# ESC.net
KiCad netlist of a schematic drawn in EAGLE
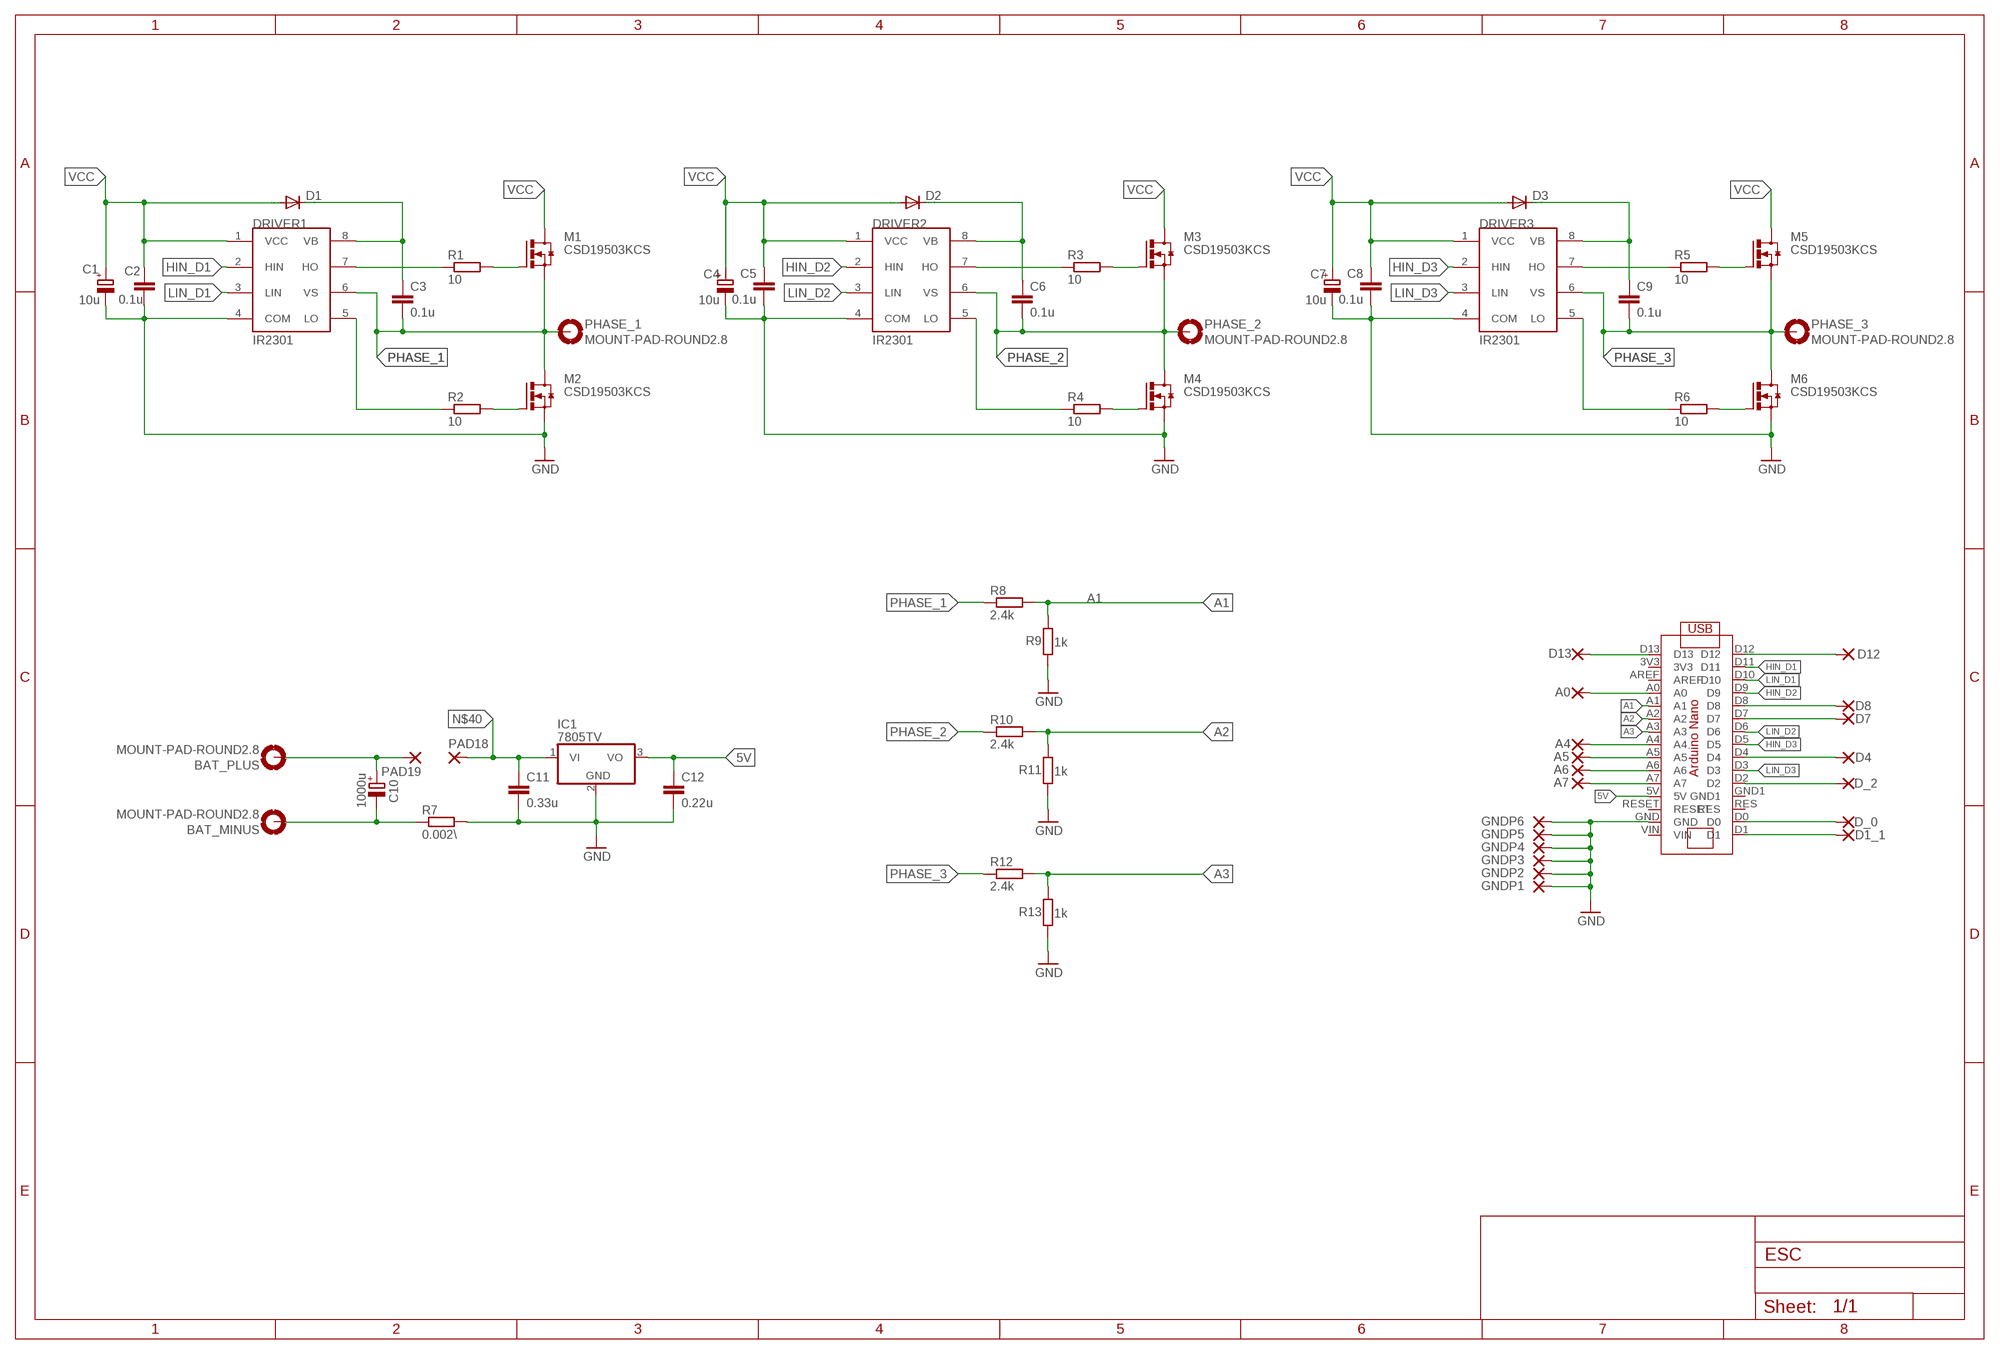
[diagram p0: schematic, sheet 1]

(export (version "E")
  (design (tool "Eeschema 10.0.6"))
  (components
    (comp (ref "A0")
      (value "3,81/1,4")
      (footprint "eagle-import:3,81_1,4")
      (libsource (lib "eagle-import") (part "3,81/1,4"))
    )
    (comp (ref "A4")
      (value "3,81/1,4")
      (footprint "eagle-import:3,81_1,4")
      (libsource (lib "eagle-import") (part "3,81/1,4"))
    )
    (comp (ref "A5")
      (value "3,81/1,4")
      (footprint "eagle-import:3,81_1,4")
      (libsource (lib "eagle-import") (part "3,81/1,4"))
    )
    (comp (ref "A6")
      (value "3,81/1,4")
      (footprint "eagle-import:3,81_1,4")
      (libsource (lib "eagle-import") (part "3,81/1,4"))
    )
    (comp (ref "A7")
      (value "3,81/1,4")
      (footprint "eagle-import:3,81_1,4")
      (libsource (lib "eagle-import") (part "3,81/1,4"))
    )
    (comp (ref "BAT_MINUS")
      (value "MOUNT-PAD-ROUND2.8")
      (footprint "eagle-import:2,8-PAD")
      (libsource (lib "eagle-import") (part "MOUNT-PAD-ROUND2.8"))
    )
    (comp (ref "BAT_PLUS")
      (value "MOUNT-PAD-ROUND2.8")
      (footprint "eagle-import:2,8-PAD")
      (libsource (lib "eagle-import") (part "MOUNT-PAD-ROUND2.8"))
    )
    (comp (ref "C1")
      (value "10u")
      (footprint "eagle-import:PANASONIC_C")
      (libsource (lib "eagle-import") (part "CPOL-EUC"))
    )
    (comp (ref "C2")
      (value "0.1u")
      (footprint "eagle-import:C1206")
      (libsource (lib "eagle-import") (part "CC1206"))
    )
    (comp (ref "C3")
      (value "0.1u")
      (footprint "eagle-import:C1206")
      (libsource (lib "eagle-import") (part "CC1206"))
    )
    (comp (ref "C4")
      (value "10u")
      (footprint "eagle-import:PANASONIC_C")
      (libsource (lib "eagle-import") (part "CPOL-EUC"))
    )
    (comp (ref "C5")
      (value "0.1u")
      (footprint "eagle-import:C1206")
      (libsource (lib "eagle-import") (part "CC1206"))
    )
    (comp (ref "C6")
      (value "0.1u")
      (footprint "eagle-import:C1206")
      (libsource (lib "eagle-import") (part "CC1206"))
    )
    (comp (ref "C7")
      (value "10u")
      (footprint "eagle-import:PANASONIC_C")
      (libsource (lib "eagle-import") (part "CPOL-EUC"))
    )
    (comp (ref "C8")
      (value "0.1u")
      (footprint "eagle-import:C1206")
      (libsource (lib "eagle-import") (part "CC1206"))
    )
    (comp (ref "C9")
      (value "0.1u")
      (footprint "eagle-import:C1206")
      (libsource (lib "eagle-import") (part "CC1206"))
    )
    (comp (ref "C10")
      (value "1000u")
      (footprint "eagle-import:E7,5-16")
      (libsource (lib "eagle-import") (part "CPOL-EUE7.5-16"))
    )
    (comp (ref "C11")
      (value "0.33u")
      (footprint "eagle-import:C1206")
      (libsource (lib "eagle-import") (part "CC1206"))
    )
    (comp (ref "C12")
      (value "0.22u")
      (footprint "eagle-import:C1206")
      (libsource (lib "eagle-import") (part "CC1206"))
    )
    (comp (ref "D1")
      (value "DIODE-DO41-10")
      (footprint "eagle-import:DO41-10")
      (libsource (lib "eagle-import") (part "DIODE-DO41-10"))
    )
    (comp (ref "D1_1")
      (value "3,81/1,4")
      (footprint "eagle-import:3,81_1,4")
      (libsource (lib "eagle-import") (part "3,81/1,4"))
    )
    (comp (ref "D2")
      (value "DIODE-DO41-10")
      (footprint "eagle-import:DO41-10")
      (libsource (lib "eagle-import") (part "DIODE-DO41-10"))
    )
    (comp (ref "D3")
      (value "DIODE-DO41-10")
      (footprint "eagle-import:DO41-10")
      (libsource (lib "eagle-import") (part "DIODE-DO41-10"))
    )
    (comp (ref "D4")
      (value "3,81/1,4")
      (footprint "eagle-import:3,81_1,4")
      (libsource (lib "eagle-import") (part "3,81/1,4"))
    )
    (comp (ref "D7")
      (value "3,81/1,4")
      (footprint "eagle-import:3,81_1,4")
      (libsource (lib "eagle-import") (part "3,81/1,4"))
    )
    (comp (ref "D8")
      (value "3,81/1,4")
      (footprint "eagle-import:3,81_1,4")
      (libsource (lib "eagle-import") (part "3,81/1,4"))
    )
    (comp (ref "D12")
      (value "3,81/1,4")
      (footprint "eagle-import:3,81_1,4")
      (libsource (lib "eagle-import") (part "3,81/1,4"))
    )
    (comp (ref "D13")
      (value "3,81/1,4")
      (footprint "eagle-import:3,81_1,4")
      (libsource (lib "eagle-import") (part "3,81/1,4"))
    )
    (comp (ref "DRIVER1")
      (value "IR2301")
      (footprint "eagle-import:DIL08")
      (fields (field (name "MF") "Infineon"))
      (libsource (lib "eagle-import") (part "IR2301"))
    )
    (comp (ref "DRIVER2")
      (value "IR2301")
      (footprint "eagle-import:DIL08")
      (fields (field (name "MF") "Infineon"))
      (libsource (lib "eagle-import") (part "IR2301"))
    )
    (comp (ref "DRIVER3")
      (value "IR2301")
      (footprint "eagle-import:DIL08")
      (fields (field (name "MF") "Infineon"))
      (libsource (lib "eagle-import") (part "IR2301"))
    )
    (comp (ref "D_0")
      (value "3,81/1,4")
      (footprint "eagle-import:3,81_1,4")
      (libsource (lib "eagle-import") (part "3,81/1,4"))
    )
    (comp (ref "D_2")
      (value "3,81/1,4")
      (footprint "eagle-import:3,81_1,4")
      (libsource (lib "eagle-import") (part "3,81/1,4"))
    )
    (comp (ref "GNDP1")
      (value "3,81/1,4")
      (footprint "eagle-import:3,81_1,4")
      (libsource (lib "eagle-import") (part "3,81/1,4"))
    )
    (comp (ref "GNDP2")
      (value "3,81/1,4")
      (footprint "eagle-import:3,81_1,4")
      (libsource (lib "eagle-import") (part "3,81/1,4"))
    )
    (comp (ref "GNDP3")
      (value "3,81/1,4")
      (footprint "eagle-import:3,81_1,4")
      (libsource (lib "eagle-import") (part "3,81/1,4"))
    )
    (comp (ref "GNDP4")
      (value "3,81/1,4")
      (footprint "eagle-import:3,81_1,4")
      (libsource (lib "eagle-import") (part "3,81/1,4"))
    )
    (comp (ref "GNDP5")
      (value "3,81/1,4")
      (footprint "eagle-import:3,81_1,4")
      (libsource (lib "eagle-import") (part "3,81/1,4"))
    )
    (comp (ref "GNDP6")
      (value "3,81/1,4")
      (footprint "eagle-import:3,81_1,4")
      (libsource (lib "eagle-import") (part "3,81/1,4"))
    )
    (comp (ref "IC1")
      (value "7805TV")
      (footprint "eagle-import:TO220V")
      (libsource (lib "eagle-import") (part "78TV05"))
    )
    (comp (ref "M1")
      (value "CSD19503KCS")
      (footprint "eagle-import:TO220BV")
      (fields (field (name "SPICEPREFIX") "M"))
      (libsource (lib "eagle-import") (part "CSD19503KCS"))
    )
    (comp (ref "M2")
      (value "CSD19503KCS")
      (footprint "eagle-import:TO220BV")
      (libsource (lib "eagle-import") (part "CSD19503KCS"))
    )
    (comp (ref "M3")
      (value "CSD19503KCS")
      (footprint "eagle-import:TO220BV")
      (libsource (lib "eagle-import") (part "CSD19503KCS"))
    )
    (comp (ref "M4")
      (value "CSD19503KCS")
      (footprint "eagle-import:TO220BV")
      (libsource (lib "eagle-import") (part "CSD19503KCS"))
    )
    (comp (ref "M5")
      (value "CSD19503KCS")
      (footprint "eagle-import:TO220BV")
      (libsource (lib "eagle-import") (part "CSD19503KCS"))
    )
    (comp (ref "M6")
      (value "CSD19503KCS")
      (footprint "eagle-import:TO220BV")
      (libsource (lib "eagle-import") (part "CSD19503KCS"))
    )
    (comp (ref "PAD18")
      (value "3,81/1,4")
      (footprint "eagle-import:3,81_1,4")
      (libsource (lib "eagle-import") (part "3,81/1,4"))
    )
    (comp (ref "PAD19")
      (value "3,81/1,4")
      (footprint "eagle-import:3,81_1,4")
      (libsource (lib "eagle-import") (part "3,81/1,4"))
    )
    (comp (ref "PHASE_1")
      (value "MOUNT-PAD-ROUND2.8")
      (footprint "eagle-import:2,8-PAD")
      (libsource (lib "eagle-import") (part "MOUNT-PAD-ROUND2.8"))
    )
    (comp (ref "PHASE_2")
      (value "MOUNT-PAD-ROUND2.8")
      (footprint "eagle-import:2,8-PAD")
      (libsource (lib "eagle-import") (part "MOUNT-PAD-ROUND2.8"))
    )
    (comp (ref "PHASE_3")
      (value "MOUNT-PAD-ROUND2.8")
      (footprint "eagle-import:2,8-PAD")
      (libsource (lib "eagle-import") (part "MOUNT-PAD-ROUND2.8"))
    )
    (comp (ref "R1")
      (value "10")
      (footprint "eagle-import:R1206")
      (libsource (lib "eagle-import") (part "R-EU_R1206"))
    )
    (comp (ref "R2")
      (value "10")
      (footprint "eagle-import:R1206")
      (libsource (lib "eagle-import") (part "R-EU_R1206"))
    )
    (comp (ref "R3")
      (value "10")
      (footprint "eagle-import:R1206")
      (libsource (lib "eagle-import") (part "R-EU_R1206"))
    )
    (comp (ref "R4")
      (value "10")
      (footprint "eagle-import:R1206")
      (libsource (lib "eagle-import") (part "R-EU_R1206"))
    )
    (comp (ref "R5")
      (value "10")
      (footprint "eagle-import:R1206")
      (libsource (lib "eagle-import") (part "R-EU_R1206"))
    )
    (comp (ref "R6")
      (value "10")
      (footprint "eagle-import:R1206")
      (libsource (lib "eagle-import") (part "R-EU_R1206"))
    )
    (comp (ref "R7")
      (value "0.002\\")
      (footprint "eagle-import:R2512")
      (libsource (lib "eagle-import") (part "R-EU_R2512"))
    )
    (comp (ref "R8")
      (value "2.4k")
      (footprint "eagle-import:R1206")
      (libsource (lib "eagle-import") (part "R-EU_R1206"))
    )
    (comp (ref "R9")
      (value "1k")
      (footprint "eagle-import:R1206")
      (libsource (lib "eagle-import") (part "R-EU_R1206"))
    )
    (comp (ref "R10")
      (value "2.4k")
      (footprint "eagle-import:R1206")
      (libsource (lib "eagle-import") (part "R-EU_R1206"))
    )
    (comp (ref "R11")
      (value "1k")
      (footprint "eagle-import:R1206")
      (libsource (lib "eagle-import") (part "R-EU_R1206"))
    )
    (comp (ref "R12")
      (value "2.4k")
      (footprint "eagle-import:R1206")
      (libsource (lib "eagle-import") (part "R-EU_R1206"))
    )
    (comp (ref "R13")
      (value "1k")
      (footprint "eagle-import:R1206")
      (libsource (lib "eagle-import") (part "R-EU_R1206"))
    )
    (comp (ref "U$7")
      (value "ARDUINO-NANO")
      (footprint "eagle-import:ARDUINO-NANO")
      (libsource (lib "eagle-import") (part "ARDUINO-NANO"))
    )
  )
  (nets
    (net (code "1") (name "5V") (class "Default")
      (node (ref "C12") (pin "1") (pinfunction "1_1") (pintype "passive"))
      (node (ref "IC1") (pin "3") (pinfunction "VO_3") (pintype "passive"))
      (node (ref "U$7") (pin "5V") (pinfunction "5V_5V") (pintype "bidirectional"))
    )
    (net (code "2") (name "A1") (class "Default")
      (node (ref "R8") (pin "2") (pinfunction "2_2") (pintype "bidirectional"))
      (node (ref "R9") (pin "2") (pinfunction "2_2") (pintype "bidirectional"))
      (node (ref "U$7") (pin "A1") (pinfunction "A1_A1") (pintype "bidirectional"))
    )
    (net (code "3") (name "A2") (class "Default")
      (node (ref "R10") (pin "2") (pinfunction "2_2") (pintype "bidirectional"))
      (node (ref "R11") (pin "2") (pinfunction "2_2") (pintype "bidirectional"))
      (node (ref "U$7") (pin "A2") (pinfunction "A2_A2") (pintype "bidirectional"))
    )
    (net (code "4") (name "A3") (class "Default")
      (node (ref "R12") (pin "2") (pinfunction "2_2") (pintype "bidirectional"))
      (node (ref "R13") (pin "2") (pinfunction "2_2") (pintype "bidirectional"))
      (node (ref "U$7") (pin "A3") (pinfunction "A3_A3") (pintype "bidirectional"))
    )
    (net (code "5") (name "GND") (class "Default")
      (node (ref "C1") (pin "-") (pinfunction "-_-") (pintype "passive"))
      (node (ref "C11") (pin "2") (pinfunction "2_2") (pintype "passive"))
      (node (ref "C12") (pin "2") (pinfunction "2_2") (pintype "passive"))
      (node (ref "C2") (pin "2") (pinfunction "2_2") (pintype "passive"))
      (node (ref "C4") (pin "-") (pinfunction "-_-") (pintype "passive"))
      (node (ref "C5") (pin "2") (pinfunction "2_2") (pintype "passive"))
      (node (ref "C7") (pin "-") (pinfunction "-_-") (pintype "passive"))
      (node (ref "C8") (pin "2") (pinfunction "2_2") (pintype "passive"))
      (node (ref "DRIVER1") (pin "4") (pinfunction "COM_4") (pintype "power_in"))
      (node (ref "DRIVER2") (pin "4") (pinfunction "COM_4") (pintype "power_in"))
      (node (ref "DRIVER3") (pin "4") (pinfunction "COM_4") (pintype "power_in"))
      (node (ref "GNDP1") (pin "1") (pinfunction "P_1") (pintype "passive"))
      (node (ref "GNDP2") (pin "1") (pinfunction "P_1") (pintype "passive"))
      (node (ref "GNDP3") (pin "1") (pinfunction "P_1") (pintype "passive"))
      (node (ref "GNDP4") (pin "1") (pinfunction "P_1") (pintype "passive"))
      (node (ref "GNDP5") (pin "1") (pinfunction "P_1") (pintype "passive"))
      (node (ref "GNDP6") (pin "1") (pinfunction "P_1") (pintype "passive"))
      (node (ref "IC1") (pin "2") (pinfunction "GND_2") (pintype "passive"))
      (node (ref "M2") (pin "S") (pinfunction "S_S") (pintype "passive"))
      (node (ref "M4") (pin "S") (pinfunction "S_S") (pintype "passive"))
      (node (ref "M6") (pin "S") (pinfunction "S_S") (pintype "passive"))
      (node (ref "R11") (pin "1") (pinfunction "1_1") (pintype "bidirectional"))
      (node (ref "R13") (pin "1") (pinfunction "1_1") (pintype "bidirectional"))
      (node (ref "R7") (pin "2") (pinfunction "2_2") (pintype "passive"))
      (node (ref "R9") (pin "1") (pinfunction "1_1") (pintype "bidirectional"))
      (node (ref "U$7") (pin "GND") (pinfunction "GND_GND") (pintype "bidirectional"))
    )
    (net (code "6") (name "HIN_D1") (class "Default")
      (node (ref "DRIVER1") (pin "2") (pinfunction "HIN_2") (pintype "input"))
      (node (ref "U$7") (pin "D11") (pinfunction "D11_D11") (pintype "bidirectional"))
    )
    (net (code "7") (name "HIN_D2") (class "Default")
      (node (ref "DRIVER2") (pin "2") (pinfunction "HIN_2") (pintype "input"))
      (node (ref "U$7") (pin "D9") (pinfunction "D9_D9") (pintype "bidirectional"))
    )
    (net (code "8") (name "HIN_D3") (class "Default")
      (node (ref "DRIVER3") (pin "2") (pinfunction "HIN_2") (pintype "input"))
      (node (ref "U$7") (pin "D5") (pinfunction "D5_D5") (pintype "bidirectional"))
    )
    (net (code "9") (name "LIN_D1") (class "Default")
      (node (ref "DRIVER1") (pin "3") (pinfunction "LIN_3") (pintype "input"))
      (node (ref "U$7") (pin "D10") (pinfunction "D10_D10") (pintype "bidirectional"))
    )
    (net (code "10") (name "LIN_D2") (class "Default")
      (node (ref "DRIVER2") (pin "3") (pinfunction "LIN_3") (pintype "input"))
      (node (ref "U$7") (pin "D6") (pinfunction "D6_D6") (pintype "bidirectional"))
    )
    (net (code "11") (name "LIN_D3") (class "Default")
      (node (ref "DRIVER3") (pin "3") (pinfunction "LIN_3") (pintype "input"))
      (node (ref "U$7") (pin "D3") (pinfunction "D3_D3") (pintype "bidirectional"))
    )
    (net (code "12") (name "N$40") (class "Default")
      (node (ref "C11") (pin "1") (pinfunction "1_1") (pintype "passive"))
      (node (ref "IC1") (pin "1") (pinfunction "VI_1") (pintype "input"))
      (node (ref "PAD18") (pin "1") (pinfunction "P_1") (pintype "passive"))
    )
    (net (code "13") (name "Net-(A0-P)") (class "Default")
      (node (ref "A0") (pin "1") (pinfunction "P_1") (pintype "passive"))
      (node (ref "U$7") (pin "A0") (pinfunction "A0_A0") (pintype "bidirectional"))
    )
    (net (code "14") (name "Net-(A4-P)") (class "Default")
      (node (ref "A4") (pin "1") (pinfunction "P_1") (pintype "passive"))
      (node (ref "U$7") (pin "A4") (pinfunction "A4_A4") (pintype "bidirectional"))
    )
    (net (code "15") (name "Net-(A5-P)") (class "Default")
      (node (ref "A5") (pin "1") (pinfunction "P_1") (pintype "passive"))
      (node (ref "U$7") (pin "A5") (pinfunction "A5_A5") (pintype "bidirectional"))
    )
    (net (code "16") (name "Net-(A6-P)") (class "Default")
      (node (ref "A6") (pin "1") (pinfunction "P_1") (pintype "passive"))
      (node (ref "U$7") (pin "A6") (pinfunction "A6_A6") (pintype "bidirectional"))
    )
    (net (code "17") (name "Net-(A7-P)") (class "Default")
      (node (ref "A7") (pin "1") (pinfunction "P_1") (pintype "passive"))
      (node (ref "U$7") (pin "A7") (pinfunction "A7_A7") (pintype "bidirectional"))
    )
    (net (code "18") (name "Net-(BAT_MINUS-MOUNT)") (class "Default")
      (node (ref "BAT_MINUS") (pin "B2,8") (pinfunction "MOUNT_B2,8") (pintype "passive"))
      (node (ref "C10") (pin "-") (pinfunction "-_-") (pintype "passive"))
      (node (ref "R7") (pin "1") (pinfunction "1_1") (pintype "passive"))
    )
    (net (code "19") (name "Net-(D1_1-P)") (class "Default")
      (node (ref "D1_1") (pin "1") (pinfunction "P_1") (pintype "passive"))
      (node (ref "U$7") (pin "D1") (pinfunction "D1_D1") (pintype "bidirectional"))
    )
    (net (code "20") (name "Net-(D4-P)") (class "Default")
      (node (ref "D4") (pin "1") (pinfunction "P_1") (pintype "passive"))
      (node (ref "U$7") (pin "D4") (pinfunction "D4_D4") (pintype "bidirectional"))
    )
    (net (code "21") (name "Net-(D7-P)") (class "Default")
      (node (ref "D7") (pin "1") (pinfunction "P_1") (pintype "passive"))
      (node (ref "U$7") (pin "D7") (pinfunction "D7_D7") (pintype "bidirectional"))
    )
    (net (code "22") (name "Net-(D8-P)") (class "Default")
      (node (ref "D8") (pin "1") (pinfunction "P_1") (pintype "passive"))
      (node (ref "U$7") (pin "D8") (pinfunction "D8_D8") (pintype "bidirectional"))
    )
    (net (code "23") (name "Net-(D12-P)") (class "Default")
      (node (ref "D12") (pin "1") (pinfunction "P_1") (pintype "passive"))
      (node (ref "U$7") (pin "D12") (pinfunction "D12_D12") (pintype "bidirectional"))
    )
    (net (code "24") (name "Net-(D13-P)") (class "Default")
      (node (ref "D13") (pin "1") (pinfunction "P_1") (pintype "passive"))
      (node (ref "U$7") (pin "D13") (pinfunction "D13_D13") (pintype "bidirectional"))
    )
    (net (code "25") (name "Net-(DRIVER1-HO)") (class "Default")
      (node (ref "DRIVER1") (pin "7") (pinfunction "HO_7") (pintype "output"))
      (node (ref "R1") (pin "1") (pinfunction "1_1") (pintype "bidirectional"))
    )
    (net (code "26") (name "Net-(DRIVER1-LO)") (class "Default")
      (node (ref "DRIVER1") (pin "5") (pinfunction "LO_5") (pintype "output"))
      (node (ref "R2") (pin "1") (pinfunction "1_1") (pintype "bidirectional"))
    )
    (net (code "27") (name "Net-(DRIVER1-VB)") (class "Default")
      (node (ref "C3") (pin "1") (pinfunction "1_1") (pintype "passive"))
      (node (ref "D1") (pin "C") (pinfunction "C_C") (pintype "passive"))
      (node (ref "DRIVER1") (pin "8") (pinfunction "VB_8") (pintype "power_in"))
    )
    (net (code "28") (name "Net-(DRIVER2-HO)") (class "Default")
      (node (ref "DRIVER2") (pin "7") (pinfunction "HO_7") (pintype "output"))
      (node (ref "R3") (pin "1") (pinfunction "1_1") (pintype "bidirectional"))
    )
    (net (code "29") (name "Net-(DRIVER2-LO)") (class "Default")
      (node (ref "DRIVER2") (pin "5") (pinfunction "LO_5") (pintype "output"))
      (node (ref "R4") (pin "1") (pinfunction "1_1") (pintype "bidirectional"))
    )
    (net (code "30") (name "Net-(DRIVER2-VB)") (class "Default")
      (node (ref "C6") (pin "1") (pinfunction "1_1") (pintype "passive"))
      (node (ref "D2") (pin "C") (pinfunction "C_C") (pintype "passive"))
      (node (ref "DRIVER2") (pin "8") (pinfunction "VB_8") (pintype "power_in"))
    )
    (net (code "31") (name "Net-(DRIVER3-HO)") (class "Default")
      (node (ref "DRIVER3") (pin "7") (pinfunction "HO_7") (pintype "output"))
      (node (ref "R5") (pin "1") (pinfunction "1_1") (pintype "bidirectional"))
    )
    (net (code "32") (name "Net-(DRIVER3-LO)") (class "Default")
      (node (ref "DRIVER3") (pin "5") (pinfunction "LO_5") (pintype "output"))
      (node (ref "R6") (pin "1") (pinfunction "1_1") (pintype "bidirectional"))
    )
    (net (code "33") (name "Net-(DRIVER3-VB)") (class "Default")
      (node (ref "C9") (pin "1") (pinfunction "1_1") (pintype "passive"))
      (node (ref "D3") (pin "C") (pinfunction "C_C") (pintype "passive"))
      (node (ref "DRIVER3") (pin "8") (pinfunction "VB_8") (pintype "power_in"))
    )
    (net (code "34") (name "Net-(D_0-P)") (class "Default")
      (node (ref "D_0") (pin "1") (pinfunction "P_1") (pintype "passive"))
      (node (ref "U$7") (pin "D0") (pinfunction "D0_D0") (pintype "bidirectional"))
    )
    (net (code "35") (name "Net-(D_2-P)") (class "Default")
      (node (ref "D_2") (pin "1") (pinfunction "P_1") (pintype "passive"))
      (node (ref "U$7") (pin "D2") (pinfunction "D2_D2") (pintype "bidirectional"))
    )
    (net (code "36") (name "Net-(M1-PadG)") (class "Default")
      (node (ref "M1") (pin "G") (pinfunction "G_G") (pintype "passive"))
      (node (ref "R1") (pin "2") (pinfunction "2_2") (pintype "bidirectional"))
    )
    (net (code "37") (name "Net-(M2-PadG)") (class "Default")
      (node (ref "M2") (pin "G") (pinfunction "G_G") (pintype "passive"))
      (node (ref "R2") (pin "2") (pinfunction "2_2") (pintype "bidirectional"))
    )
    (net (code "38") (name "Net-(M3-PadG)") (class "Default")
      (node (ref "M3") (pin "G") (pinfunction "G_G") (pintype "passive"))
      (node (ref "R3") (pin "2") (pinfunction "2_2") (pintype "bidirectional"))
    )
    (net (code "39") (name "Net-(M4-PadG)") (class "Default")
      (node (ref "M4") (pin "G") (pinfunction "G_G") (pintype "passive"))
      (node (ref "R4") (pin "2") (pinfunction "2_2") (pintype "bidirectional"))
    )
    (net (code "40") (name "Net-(M5-PadG)") (class "Default")
      (node (ref "M5") (pin "G") (pinfunction "G_G") (pintype "passive"))
      (node (ref "R5") (pin "2") (pinfunction "2_2") (pintype "bidirectional"))
    )
    (net (code "41") (name "Net-(M6-PadG)") (class "Default")
      (node (ref "M6") (pin "G") (pinfunction "G_G") (pintype "passive"))
      (node (ref "R6") (pin "2") (pinfunction "2_2") (pintype "bidirectional"))
    )
    (net (code "42") (name "PHASE_1") (class "Default")
      (node (ref "C3") (pin "2") (pinfunction "2_2") (pintype "passive"))
      (node (ref "DRIVER1") (pin "6") (pinfunction "VS_6") (pintype "output"))
      (node (ref "M1") (pin "S") (pinfunction "S_S") (pintype "passive"))
      (node (ref "M2") (pin "D") (pinfunction "D_D") (pintype "passive"))
      (node (ref "PHASE_1") (pin "B2,8") (pinfunction "MOUNT_B2,8") (pintype "passive"))
      (node (ref "R8") (pin "1") (pinfunction "1_1") (pintype "bidirectional"))
    )
    (net (code "43") (name "PHASE_2") (class "Default")
      (node (ref "C6") (pin "2") (pinfunction "2_2") (pintype "passive"))
      (node (ref "DRIVER2") (pin "6") (pinfunction "VS_6") (pintype "output"))
      (node (ref "M3") (pin "S") (pinfunction "S_S") (pintype "passive"))
      (node (ref "M4") (pin "D") (pinfunction "D_D") (pintype "passive"))
      (node (ref "PHASE_2") (pin "B2,8") (pinfunction "MOUNT_B2,8") (pintype "passive"))
      (node (ref "R10") (pin "1") (pinfunction "1_1") (pintype "bidirectional"))
    )
    (net (code "44") (name "PHASE_3") (class "Default")
      (node (ref "C9") (pin "2") (pinfunction "2_2") (pintype "passive"))
      (node (ref "DRIVER3") (pin "6") (pinfunction "VS_6") (pintype "output"))
      (node (ref "M5") (pin "S") (pinfunction "S_S") (pintype "passive"))
      (node (ref "M6") (pin "D") (pinfunction "D_D") (pintype "passive"))
      (node (ref "PHASE_3") (pin "B2,8") (pinfunction "MOUNT_B2,8") (pintype "passive"))
      (node (ref "R12") (pin "1") (pinfunction "1_1") (pintype "bidirectional"))
    )
    (net (code "45") (name "VCC") (class "Default")
      (node (ref "BAT_PLUS") (pin "B2,8") (pinfunction "MOUNT_B2,8") (pintype "passive"))
      (node (ref "C1") (pin "+") (pinfunction "+_+") (pintype "passive"))
      (node (ref "C10") (pin "+") (pinfunction "+_+") (pintype "passive"))
      (node (ref "C2") (pin "1") (pinfunction "1_1") (pintype "passive"))
      (node (ref "C4") (pin "+") (pinfunction "+_+") (pintype "passive"))
      (node (ref "C5") (pin "1") (pinfunction "1_1") (pintype "passive"))
      (node (ref "C7") (pin "+") (pinfunction "+_+") (pintype "passive"))
      (node (ref "C8") (pin "1") (pinfunction "1_1") (pintype "passive"))
      (node (ref "D1") (pin "A") (pinfunction "A_A") (pintype "passive"))
      (node (ref "D2") (pin "A") (pinfunction "A_A") (pintype "passive"))
      (node (ref "D3") (pin "A") (pinfunction "A_A") (pintype "passive"))
      (node (ref "DRIVER1") (pin "1") (pinfunction "VCC_1") (pintype "power_in"))
      (node (ref "DRIVER2") (pin "1") (pinfunction "VCC_1") (pintype "power_in"))
      (node (ref "DRIVER3") (pin "1") (pinfunction "VCC_1") (pintype "power_in"))
      (node (ref "M1") (pin "D") (pinfunction "D_D") (pintype "passive"))
      (node (ref "M3") (pin "D") (pinfunction "D_D") (pintype "passive"))
      (node (ref "M5") (pin "D") (pinfunction "D_D") (pintype "passive"))
      (node (ref "PAD19") (pin "1") (pinfunction "P_1") (pintype "passive"))
    )
    (net (code "46") (name "unconnected-(U$7-Pad3V3)") (class "Default")
      (node (ref "U$7") (pin "3V3") (pinfunction "3V3_3V3") (pintype "bidirectional"))
    )
    (net (code "47") (name "unconnected-(U$7-PadAREF)") (class "Default")
      (node (ref "U$7") (pin "AREF") (pinfunction "AREF_AREF") (pintype "bidirectional"))
    )
    (net (code "48") (name "unconnected-(U$7-PadGND1)") (class "Default")
      (node (ref "U$7") (pin "GND1") (pinfunction "GND1_GND1") (pintype "bidirectional"))
    )
    (net (code "49") (name "unconnected-(U$7-PadRES)") (class "Default")
      (node (ref "U$7") (pin "RES") (pinfunction "RES_RES") (pintype "bidirectional"))
    )
    (net (code "50") (name "unconnected-(U$7-PadRESET)") (class "Default")
      (node (ref "U$7") (pin "RESET") (pinfunction "RESET_RESET") (pintype "bidirectional"))
    )
    (net (code "51") (name "unconnected-(U$7-PadVIN)") (class "Default")
      (node (ref "U$7") (pin "VIN") (pinfunction "VIN_VIN") (pintype "bidirectional"))
    )
  )
)
